# PID.net
KiCad netlist of a schematic drawn in Altium Designer
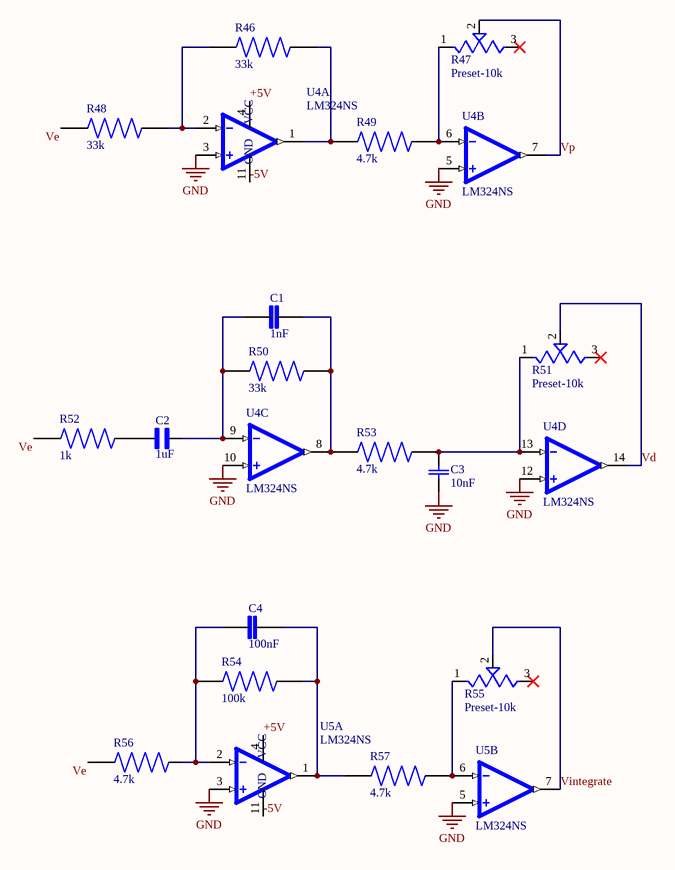
[diagram p0: PID.SchDoc]

(export (version "E")
  (design (tool "Eeschema 10.0.6"))
  (components
    (comp (ref "C1")
      (value "1nF")
      (footprint "CAPC2012X70")
      (description "1000 pF Â±10% 50V Ceramic Capacitor X7R 0805 (2012 Metric); CC0805KRX7R9BB102")
      (fields (field (name "MF") "Yageo") (field (name "MP") "CC0805KRX7R9BB102"))
      (libsource (lib "1nfs") (part "1nF"))
    )
    (comp (ref "C2")
      (value "1uF")
      (footprint "CAPC2012X135N")
      (description "SMD Capacitor X7R(EIA) with Capacitance: 1.0uF Tol. 10%. Rated Voltage: 25Vdc; GRM21BR71E105KA99L")
      (fields (field (name "MF") "Murata") (field (name "MP") "GRM21BR71E105KA99L"))
      (libsource (lib "1ufs") (part "1uF"))
    )
    (comp (ref "C3")
      (value "10nF")
      (footprint "CAPC2013X110N")
      (description "10000 pF Â±10% 50V Ceramic Capacitor X7R 0805 (2012 Metric); CC0805KRX7R9BB103")
      (fields (field (name "MF") "Yageo") (field (name "MP") "CC0805KRX7R9BB103"))
      (libsource (lib "10nfs") (part "10nF"))
    )
    (comp (ref "C4")
      (value "100nF")
      (footprint "CAPC2012X70")
      (description "1000 pF Â±10% 50V Ceramic Capacitor X7R 0805 (2012 Metric); CC0805KRX7R9BB102")
      (fields (field (name "MF") "Yageo") (field (name "MP") "CC0805KRX7R9BB102"))
      (libsource (lib "1nfs") (part "1nF"))
    )
    (comp (ref "R46")
      (value "33k")
      (footprint "RESC2012X60N")
      (fields (field (name "MF") "Yageo") (field (name "MP") "RC0805FR-0733KL"))
      (libsource (lib "33ks") (part "33k"))
    )
    (comp (ref "R47")
      (value "Preset-10k")
      (footprint "TRIM_3306F-1-103")
      (description "TRIMMER - 6MM ROUND, SINGLE-TURN,CERMET, 10K OHMS ¦ Bourns 3306F-1-103")
      (fields (field (name "MF") "Bourns") (field (name "MP") "3306F-1-103"))
      (libsource (lib "3306F-1-103") (part "Preset"))
    )
    (comp (ref "R48")
      (value "33k")
      (footprint "RESC2012X60N")
      (fields (field (name "MF") "Yageo") (field (name "MP") "RC0805FR-0733KL"))
      (libsource (lib "33ks") (part "33k"))
    )
    (comp (ref "R49")
      (value "4.7k")
      (footprint "RESC2012X60N")
      (fields (field (name "MP") "RC0805FR-074K7L") (field (name "MF") "Yageo"))
      (libsource (lib "4 7ks") (part "4.7k"))
    )
    (comp (ref "R50")
      (value "33k")
      (footprint "RESC2012X60N")
      (fields (field (name "MF") "Yageo") (field (name "MP") "RC0805FR-0733KL"))
      (libsource (lib "33ks") (part "33k"))
    )
    (comp (ref "R51")
      (value "Preset-10k")
      (footprint "TRIM_3306F-1-103")
      (description "TRIMMER - 6MM ROUND, SINGLE-TURN,CERMET, 10K OHMS ¦ Bourns 3306F-1-103")
      (fields (field (name "MF") "Bourns") (field (name "MP") "3306F-1-103"))
      (libsource (lib "3306F-1-103") (part "Preset"))
    )
    (comp (ref "R52")
      (value "1k")
      (footprint "RESC2012X60N")
      (fields
        (field (name "DIGIKEY_PART_NUMBER") "311-1.00KCRTR-ND")
        (field (name "MF") "Yageo")
        (field (name "MP") "RC0805FR-071KL")
      )
      (libsource (lib "1ks") (part "1k"))
    )
    (comp (ref "R53")
      (value "4.7k")
      (footprint "RESC2012X60N")
      (fields (field (name "MP") "RC0805FR-074K7L") (field (name "MF") "Yageo"))
      (libsource (lib "4 7ks") (part "4.7k"))
    )
    (comp (ref "R54")
      (value "100k")
      (footprint "RESC2012X60N")
      (fields (field (name "MF") "Yageo") (field (name "MP") "RC0805FR-07100KL"))
      (libsource (lib "100ks") (part "100k"))
    )
    (comp (ref "R55")
      (value "Preset-10k")
      (footprint "TRIM_3306F-1-103")
      (description "TRIMMER - 6MM ROUND, SINGLE-TURN,CERMET, 10K OHMS ¦ Bourns 3306F-1-103")
      (fields (field (name "MF") "Bourns") (field (name "MP") "3306F-1-103"))
      (libsource (lib "3306F-1-103") (part "Preset"))
    )
    (comp (ref "R56")
      (value "4.7k")
      (footprint "RESC2012X60N")
      (fields (field (name "MP") "RC0805FR-074K7L") (field (name "MF") "Yageo"))
      (libsource (lib "4 7ks") (part "4.7k"))
    )
    (comp (ref "R57")
      (value "4.7k")
      (footprint "RESC2012X60N")
      (fields (field (name "MP") "RC0805FR-074K7L") (field (name "MF") "Yageo"))
      (libsource (lib "4 7ks") (part "4.7k"))
    )
    (comp (ref "U4")
      (value "LM324NS")
      (footprint "SOIC127P780X200-14N")
      (description "4-Channel industry standard operational amplifier 14-SO 0 to 70; LM324NSRG4")
      (fields (field (name "MP") "LM324NSRG4") (field (name "MF") "Texas Instruments"))
      (libsource (lib "LM324NSRG4") (part "LM324NS"))
    )
    (comp (ref "U5")
      (value "LM324NS")
      (footprint "SOIC127P780X200-14N")
      (description "4-Channel industry standard operational amplifier 14-SO 0 to 70; LM324NSRG4")
      (fields (field (name "MP") "LM324NSRG4") (field (name "MF") "Texas Instruments"))
      (libsource (lib "LM324NSRG4") (part "LM324NS"))
    )
  )
  (nets
    (net (code "1") (name "/+5V") (class "Default")
      (node (ref "U4") (pin "4") (pinfunction "VCC_4") (pintype "power_in"))
      (node (ref "U5") (pin "4") (pinfunction "VCC_4") (pintype "power_in"))
    )
    (net (code "2") (name "/-5V") (class "Default")
      (node (ref "U4") (pin "11") (pinfunction "GND_11") (pintype "power_in"))
      (node (ref "U5") (pin "11") (pinfunction "GND_11") (pintype "power_in"))
    )
    (net (code "3") (name "/Vd") (class "Default")
      (node (ref "R51") (pin "2") (pinfunction "W_2") (pintype "passive"))
      (node (ref "U4") (pin "14") (pinfunction "4OUT_14") (pintype "output"))
    )
    (net (code "4") (name "/Ve") (class "Default")
      (node (ref "R48") (pin "1") (pinfunction "1_1") (pintype "passive"))
      (node (ref "R52") (pin "1") (pinfunction "1_1") (pintype "passive"))
      (node (ref "R56") (pin "1") (pinfunction "1_1") (pintype "passive"))
    )
    (net (code "5") (name "/Vintegrate") (class "Default")
      (node (ref "R55") (pin "2") (pinfunction "W_2") (pintype "passive"))
      (node (ref "U5") (pin "7") (pinfunction "2OUT_7") (pintype "output"))
    )
    (net (code "6") (name "/Vp") (class "Default")
      (node (ref "R47") (pin "2") (pinfunction "W_2") (pintype "passive"))
      (node (ref "U4") (pin "7") (pinfunction "2OUT_7") (pintype "output"))
    )
    (net (code "7") (name "GND") (class "Default")
      (node (ref "C3") (pin "1") (pinfunction "C1_1") (pintype "passive"))
      (node (ref "U4") (pin "10") (pinfunction "3IN+_10") (pintype "input"))
      (node (ref "U4") (pin "12") (pinfunction "4IN+_12") (pintype "input"))
      (node (ref "U4") (pin "3") (pinfunction "1IN+_3") (pintype "input"))
      (node (ref "U4") (pin "5") (pinfunction "2IN+_5") (pintype "input"))
      (node (ref "U5") (pin "3") (pinfunction "1IN+_3") (pintype "input"))
      (node (ref "U5") (pin "5") (pinfunction "2IN+_5") (pintype "input"))
    )
    (net (code "8") (name "Net-(C2-Pad2)") (class "Default")
      (node (ref "C2") (pin "2") (pinfunction "2_2") (pintype "passive"))
      (node (ref "R52") (pin "2") (pinfunction "2_2") (pintype "passive"))
    )
    (net (code "9") (name "Net-(C3-C2)") (class "Default")
      (node (ref "C3") (pin "2") (pinfunction "C2_2") (pintype "passive"))
      (node (ref "R51") (pin "1") (pinfunction "CCW_1") (pintype "passive"))
      (node (ref "R53") (pin "2") (pinfunction "2_2") (pintype "passive"))
      (node (ref "U4") (pin "13") (pinfunction "4IN-_13") (pintype "input"))
    )
    (net (code "10") (name "Net-(R47-CCW)") (class "Default")
      (node (ref "R47") (pin "1") (pinfunction "CCW_1") (pintype "passive"))
      (node (ref "R49") (pin "2") (pinfunction "2_2") (pintype "passive"))
      (node (ref "U4") (pin "6") (pinfunction "2IN-_6") (pintype "input"))
    )
    (net (code "11") (name "Net-(R55-CCW)") (class "Default")
      (node (ref "R55") (pin "1") (pinfunction "CCW_1") (pintype "passive"))
      (node (ref "R57") (pin "2") (pinfunction "2_2") (pintype "passive"))
      (node (ref "U5") (pin "6") (pinfunction "2IN-_6") (pintype "input"))
    )
    (net (code "12") (name "Net-(U4A-1IN-)") (class "Default")
      (node (ref "R46") (pin "1") (pinfunction "1_1") (pintype "passive"))
      (node (ref "R48") (pin "2") (pinfunction "2_2") (pintype "passive"))
      (node (ref "U4") (pin "2") (pinfunction "1IN-_2") (pintype "input"))
    )
    (net (code "13") (name "Net-(U4A-1OUT)") (class "Default")
      (node (ref "R46") (pin "2") (pinfunction "2_2") (pintype "passive"))
      (node (ref "R49") (pin "1") (pinfunction "1_1") (pintype "passive"))
      (node (ref "U4") (pin "1") (pinfunction "1OUT_1") (pintype "output"))
    )
    (net (code "14") (name "Net-(U4C-3IN-)") (class "Default")
      (node (ref "C1") (pin "1") (pinfunction "1_1") (pintype "passive"))
      (node (ref "C2") (pin "1") (pinfunction "1_1") (pintype "passive"))
      (node (ref "R50") (pin "1") (pinfunction "1_1") (pintype "passive"))
      (node (ref "U4") (pin "9") (pinfunction "3IN-_9") (pintype "input"))
    )
    (net (code "15") (name "Net-(U4C-3OUT)") (class "Default")
      (node (ref "C1") (pin "2") (pinfunction "2_2") (pintype "passive"))
      (node (ref "R50") (pin "2") (pinfunction "2_2") (pintype "passive"))
      (node (ref "R53") (pin "1") (pinfunction "1_1") (pintype "passive"))
      (node (ref "U4") (pin "8") (pinfunction "3OUT_8") (pintype "output"))
    )
    (net (code "16") (name "Net-(U5A-1IN-)") (class "Default")
      (node (ref "C4") (pin "1") (pinfunction "1_1") (pintype "passive"))
      (node (ref "R54") (pin "1") (pinfunction "1_1") (pintype "passive"))
      (node (ref "R56") (pin "2") (pinfunction "2_2") (pintype "passive"))
      (node (ref "U5") (pin "2") (pinfunction "1IN-_2") (pintype "input"))
    )
    (net (code "17") (name "Net-(U5A-1OUT)") (class "Default")
      (node (ref "C4") (pin "2") (pinfunction "2_2") (pintype "passive"))
      (node (ref "R54") (pin "2") (pinfunction "2_2") (pintype "passive"))
      (node (ref "R57") (pin "1") (pinfunction "1_1") (pintype "passive"))
      (node (ref "U5") (pin "1") (pinfunction "1OUT_1") (pintype "output"))
    )
    (net (code "18") (name "unconnected-(R47-CW-Pad3)") (class "Default")
      (node (ref "R47") (pin "3") (pinfunction "CW_3") (pintype "passive+no_connect"))
    )
    (net (code "19") (name "unconnected-(R51-CW-Pad3)") (class "Default")
      (node (ref "R51") (pin "3") (pinfunction "CW_3") (pintype "passive+no_connect"))
    )
    (net (code "20") (name "unconnected-(R55-CW-Pad3)") (class "Default")
      (node (ref "R55") (pin "3") (pinfunction "CW_3") (pintype "passive+no_connect"))
    )
  )
)
